# Bluepill-V001.net
KiCad netlist of a schematic drawn in EAGLE
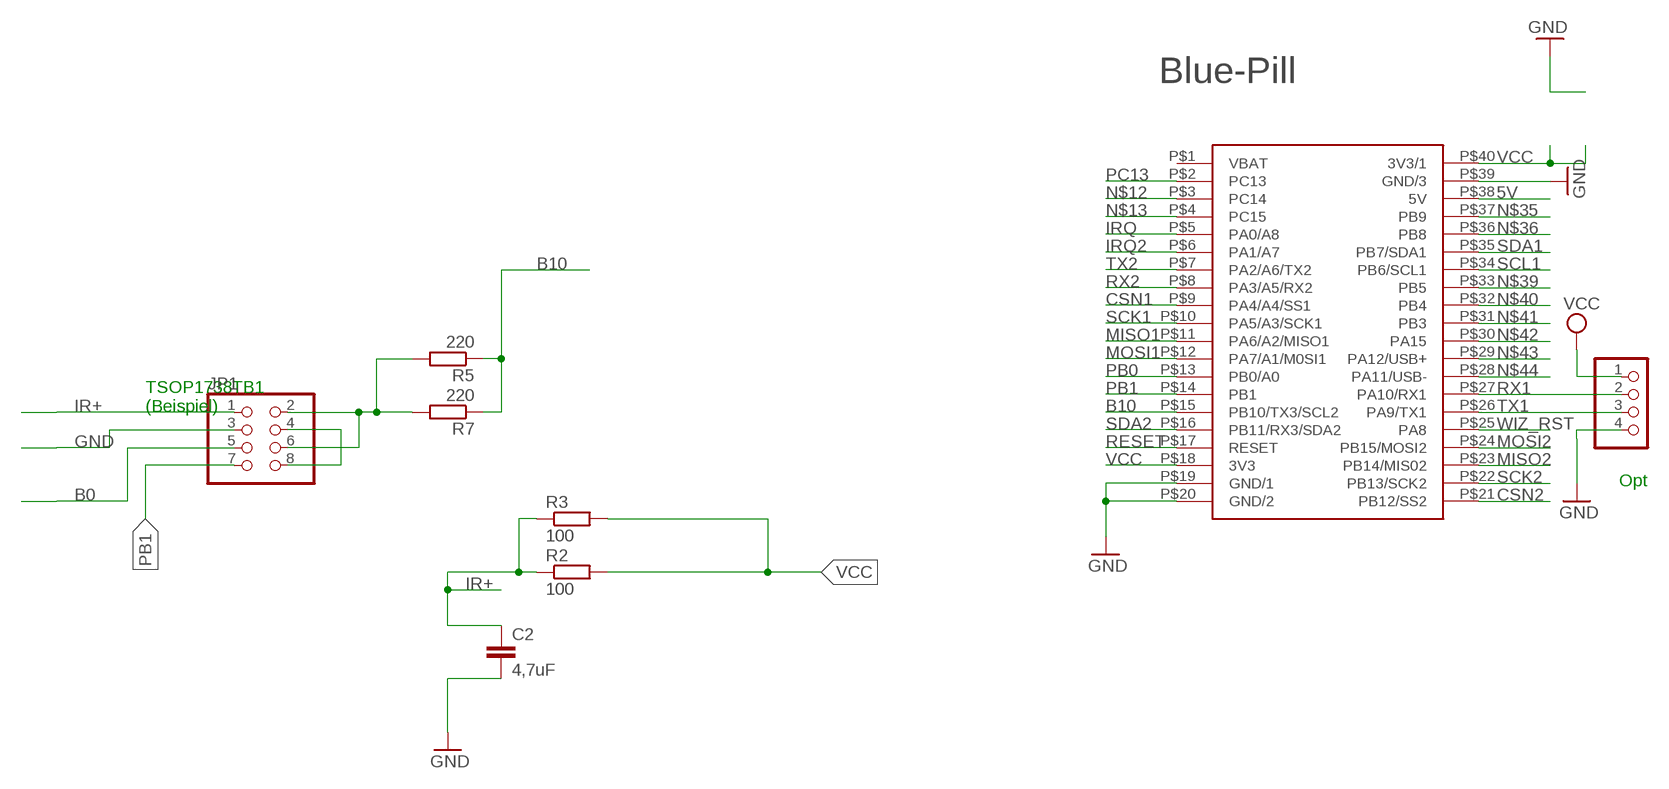
[diagram p0: schematic, sheet 1]

(export (version "E")
  (design (tool "Eeschema 10.0.6"))
  (components
    (comp (ref "C2")
      (value "4,7uF")
      (footprint "eagle-import:C1206K")
      (libsource (lib "eagle-import") (part "C-EUC1206K"))
    )
    (comp (ref "DBG")
      (value "PINHD-1X04_2.54-S")
      (footprint "eagle-import:1X04-S")
      (libsource (lib "eagle-import") (part "PINHD-1X04_2.54-S"))
    )
    (comp (ref "JP1")
      (value "PINHD-2X4/90")
      (footprint "eagle-import:2X04_90")
      (libsource (lib "eagle-import") (part "PINHD-2X4/90"))
    )
    (comp (ref "R2")
      (value "100")
      (footprint "eagle-import:0204_7")
      (libsource (lib "eagle-import") (part "R-EU_0204/7"))
    )
    (comp (ref "R3")
      (value "100")
      (footprint "eagle-import:R0805W")
      (libsource (lib "eagle-import") (part "R-EU_R0805W"))
    )
    (comp (ref "R5")
      (value "220")
      (footprint "eagle-import:0204_7")
      (libsource (lib "eagle-import") (part "R-EU_0204/7"))
    )
    (comp (ref "R7")
      (value "220")
      (footprint "eagle-import:R0805W")
      (libsource (lib "eagle-import") (part "R-EU_R0805W"))
    )
    (comp (ref "U$4")
      (value "BLUEPILL")
      (footprint "eagle-import:BLUEPILL")
      (libsource (lib "eagle-import") (part "BLUEPILL"))
    )
  )
  (nets
    (net (code "1") (name "/5V") (class "Default")
      (node (ref "U$4") (pin "P$38") (pinfunction "5V_P$38") (pintype "bidirectional"))
    )
    (net (code "2") (name "/B0") (class "Default")
      (node (ref "JP1") (pin "5") (pinfunction "5_5") (pintype "passive"))
    )
    (net (code "3") (name "/B10") (class "Default")
      (node (ref "R5") (pin "1") (pinfunction "1_1") (pintype "passive"))
      (node (ref "R7") (pin "1") (pinfunction "1_1") (pintype "passive"))
      (node (ref "U$4") (pin "P$15") (pinfunction "PB10/TX3/SCL2_P$15") (pintype "bidirectional"))
    )
    (net (code "4") (name "/CSN1") (class "Default")
      (node (ref "U$4") (pin "P$9") (pinfunction "PA4/A4/SS1_P$9") (pintype "bidirectional"))
    )
    (net (code "5") (name "/CSN2") (class "Default")
      (node (ref "U$4") (pin "P$21") (pinfunction "PB12/SS2_P$21") (pintype "bidirectional"))
    )
    (net (code "6") (name "/IR+") (class "Default")
      (node (ref "C2") (pin "1") (pinfunction "1_1") (pintype "passive"))
      (node (ref "JP1") (pin "1") (pinfunction "1_1") (pintype "passive"))
      (node (ref "R2") (pin "1") (pinfunction "1_1") (pintype "passive"))
      (node (ref "R3") (pin "1") (pinfunction "1_1") (pintype "passive"))
    )
    (net (code "7") (name "/IRQ") (class "Default")
      (node (ref "U$4") (pin "P$5") (pinfunction "PA0/A8_P$5") (pintype "bidirectional"))
    )
    (net (code "8") (name "/IRQ2") (class "Default")
      (node (ref "U$4") (pin "P$6") (pinfunction "PA1/A7_P$6") (pintype "bidirectional"))
    )
    (net (code "9") (name "/MISO1") (class "Default")
      (node (ref "U$4") (pin "P$11") (pinfunction "PA6/A2/MISO1_P$11") (pintype "bidirectional"))
    )
    (net (code "10") (name "/MISO2") (class "Default")
      (node (ref "U$4") (pin "P$23") (pinfunction "PB14/MIS02_P$23") (pintype "bidirectional"))
    )
    (net (code "11") (name "/MOSI1") (class "Default")
      (node (ref "U$4") (pin "P$12") (pinfunction "PA7/A1/M0SI1_P$12") (pintype "bidirectional"))
    )
    (net (code "12") (name "/MOSI2") (class "Default")
      (node (ref "U$4") (pin "P$24") (pinfunction "PB15/MOSI2_P$24") (pintype "bidirectional"))
    )
    (net (code "13") (name "/N$12") (class "Default")
      (node (ref "U$4") (pin "P$3") (pinfunction "PC14_P$3") (pintype "bidirectional"))
    )
    (net (code "14") (name "/N$13") (class "Default")
      (node (ref "U$4") (pin "P$4") (pinfunction "PC15_P$4") (pintype "bidirectional"))
    )
    (net (code "15") (name "/N$35") (class "Default")
      (node (ref "U$4") (pin "P$37") (pinfunction "PB9_P$37") (pintype "bidirectional"))
    )
    (net (code "16") (name "/N$36") (class "Default")
      (node (ref "U$4") (pin "P$36") (pinfunction "PB8_P$36") (pintype "bidirectional"))
    )
    (net (code "17") (name "/N$39") (class "Default")
      (node (ref "U$4") (pin "P$33") (pinfunction "PB5_P$33") (pintype "bidirectional"))
    )
    (net (code "18") (name "/N$40") (class "Default")
      (node (ref "U$4") (pin "P$32") (pinfunction "PB4_P$32") (pintype "bidirectional"))
    )
    (net (code "19") (name "/N$41") (class "Default")
      (node (ref "U$4") (pin "P$31") (pinfunction "PB3_P$31") (pintype "bidirectional"))
    )
    (net (code "20") (name "/N$42") (class "Default")
      (node (ref "U$4") (pin "P$30") (pinfunction "PA15_P$30") (pintype "bidirectional"))
    )
    (net (code "21") (name "/N$43") (class "Default")
      (node (ref "U$4") (pin "P$29") (pinfunction "PA12/USB+_P$29") (pintype "bidirectional"))
    )
    (net (code "22") (name "/N$44") (class "Default")
      (node (ref "U$4") (pin "P$28") (pinfunction "PA11/USB-_P$28") (pintype "bidirectional"))
    )
    (net (code "23") (name "/PB0") (class "Default")
      (node (ref "U$4") (pin "P$13") (pinfunction "PB0/A0_P$13") (pintype "bidirectional"))
    )
    (net (code "24") (name "/PC13") (class "Default")
      (node (ref "U$4") (pin "P$2") (pinfunction "PC13_P$2") (pintype "bidirectional"))
    )
    (net (code "25") (name "/RESET") (class "Default")
      (node (ref "U$4") (pin "P$17") (pinfunction "RESET_P$17") (pintype "bidirectional"))
    )
    (net (code "26") (name "/RX1") (class "Default")
      (node (ref "DBG") (pin "2") (pinfunction "2_2") (pintype "passive"))
      (node (ref "U$4") (pin "P$27") (pinfunction "PA10/RX1_P$27") (pintype "bidirectional"))
    )
    (net (code "27") (name "/RX2") (class "Default")
      (node (ref "U$4") (pin "P$8") (pinfunction "PA3/A5/RX2_P$8") (pintype "bidirectional"))
    )
    (net (code "28") (name "/SCK1") (class "Default")
      (node (ref "U$4") (pin "P$10") (pinfunction "PA5/A3/SCK1_P$10") (pintype "bidirectional"))
    )
    (net (code "29") (name "/SCK2") (class "Default")
      (node (ref "U$4") (pin "P$22") (pinfunction "PB13/SCK2_P$22") (pintype "bidirectional"))
    )
    (net (code "30") (name "/SCL1") (class "Default")
      (node (ref "U$4") (pin "P$34") (pinfunction "PB6/SCL1_P$34") (pintype "bidirectional"))
    )
    (net (code "31") (name "/SDA1") (class "Default")
      (node (ref "U$4") (pin "P$35") (pinfunction "PB7/SDA1_P$35") (pintype "bidirectional"))
    )
    (net (code "32") (name "/SDA2") (class "Default")
      (node (ref "U$4") (pin "P$16") (pinfunction "PB11/RX3/SDA2_P$16") (pintype "bidirectional"))
    )
    (net (code "33") (name "/TX1") (class "Default")
      (node (ref "DBG") (pin "3") (pinfunction "3_3") (pintype "passive"))
      (node (ref "U$4") (pin "P$26") (pinfunction "PA9/TX1_P$26") (pintype "bidirectional"))
    )
    (net (code "34") (name "/TX2") (class "Default")
      (node (ref "U$4") (pin "P$7") (pinfunction "PA2/A6/TX2_P$7") (pintype "bidirectional"))
    )
    (net (code "35") (name "/WIZ_RST") (class "Default")
      (node (ref "U$4") (pin "P$25") (pinfunction "PA8_P$25") (pintype "bidirectional"))
    )
    (net (code "36") (name "GND") (class "Default")
      (node (ref "C2") (pin "2") (pinfunction "2_2") (pintype "passive"))
      (node (ref "DBG") (pin "4") (pinfunction "4_4") (pintype "passive"))
      (node (ref "JP1") (pin "3") (pinfunction "3_3") (pintype "passive"))
      (node (ref "U$4") (pin "P$19") (pinfunction "GND/1_P$19") (pintype "bidirectional"))
      (node (ref "U$4") (pin "P$20") (pinfunction "GND/2_P$20") (pintype "bidirectional"))
      (node (ref "U$4") (pin "P$39") (pinfunction "GND/3_P$39") (pintype "bidirectional"))
    )
    (net (code "37") (name "Net-(JP1-Pad2)") (class "Default")
      (node (ref "JP1") (pin "2") (pinfunction "2_2") (pintype "passive"))
      (node (ref "JP1") (pin "6") (pinfunction "6_6") (pintype "passive"))
      (node (ref "R5") (pin "2") (pinfunction "2_2") (pintype "passive"))
      (node (ref "R7") (pin "2") (pinfunction "2_2") (pintype "passive"))
    )
    (net (code "38") (name "Net-(JP1-Pad4)") (class "Default")
      (node (ref "JP1") (pin "4") (pinfunction "4_4") (pintype "passive"))
      (node (ref "JP1") (pin "8") (pinfunction "8_8") (pintype "passive"))
    )
    (net (code "39") (name "PB1") (class "Default")
      (node (ref "JP1") (pin "7") (pinfunction "7_7") (pintype "passive"))
      (node (ref "U$4") (pin "P$14") (pinfunction "PB1_P$14") (pintype "bidirectional"))
    )
    (net (code "40") (name "VCC") (class "Default")
      (node (ref "DBG") (pin "1") (pinfunction "1_1") (pintype "passive"))
      (node (ref "R2") (pin "2") (pinfunction "2_2") (pintype "passive"))
      (node (ref "R3") (pin "2") (pinfunction "2_2") (pintype "passive"))
      (node (ref "U$4") (pin "P$18") (pinfunction "3V3_P$18") (pintype "bidirectional"))
      (node (ref "U$4") (pin "P$40") (pinfunction "3V3/1_P$40") (pintype "bidirectional"))
    )
    (net (code "41") (name "unconnected-(U$4-VBAT-PadP$1)") (class "Default")
      (node (ref "U$4") (pin "P$1") (pinfunction "VBAT_P$1") (pintype "bidirectional"))
    )
  )
)
